# Akustikk_forsterkerkrets.net
KiCad netlist of a schematic drawn in Altium Designer
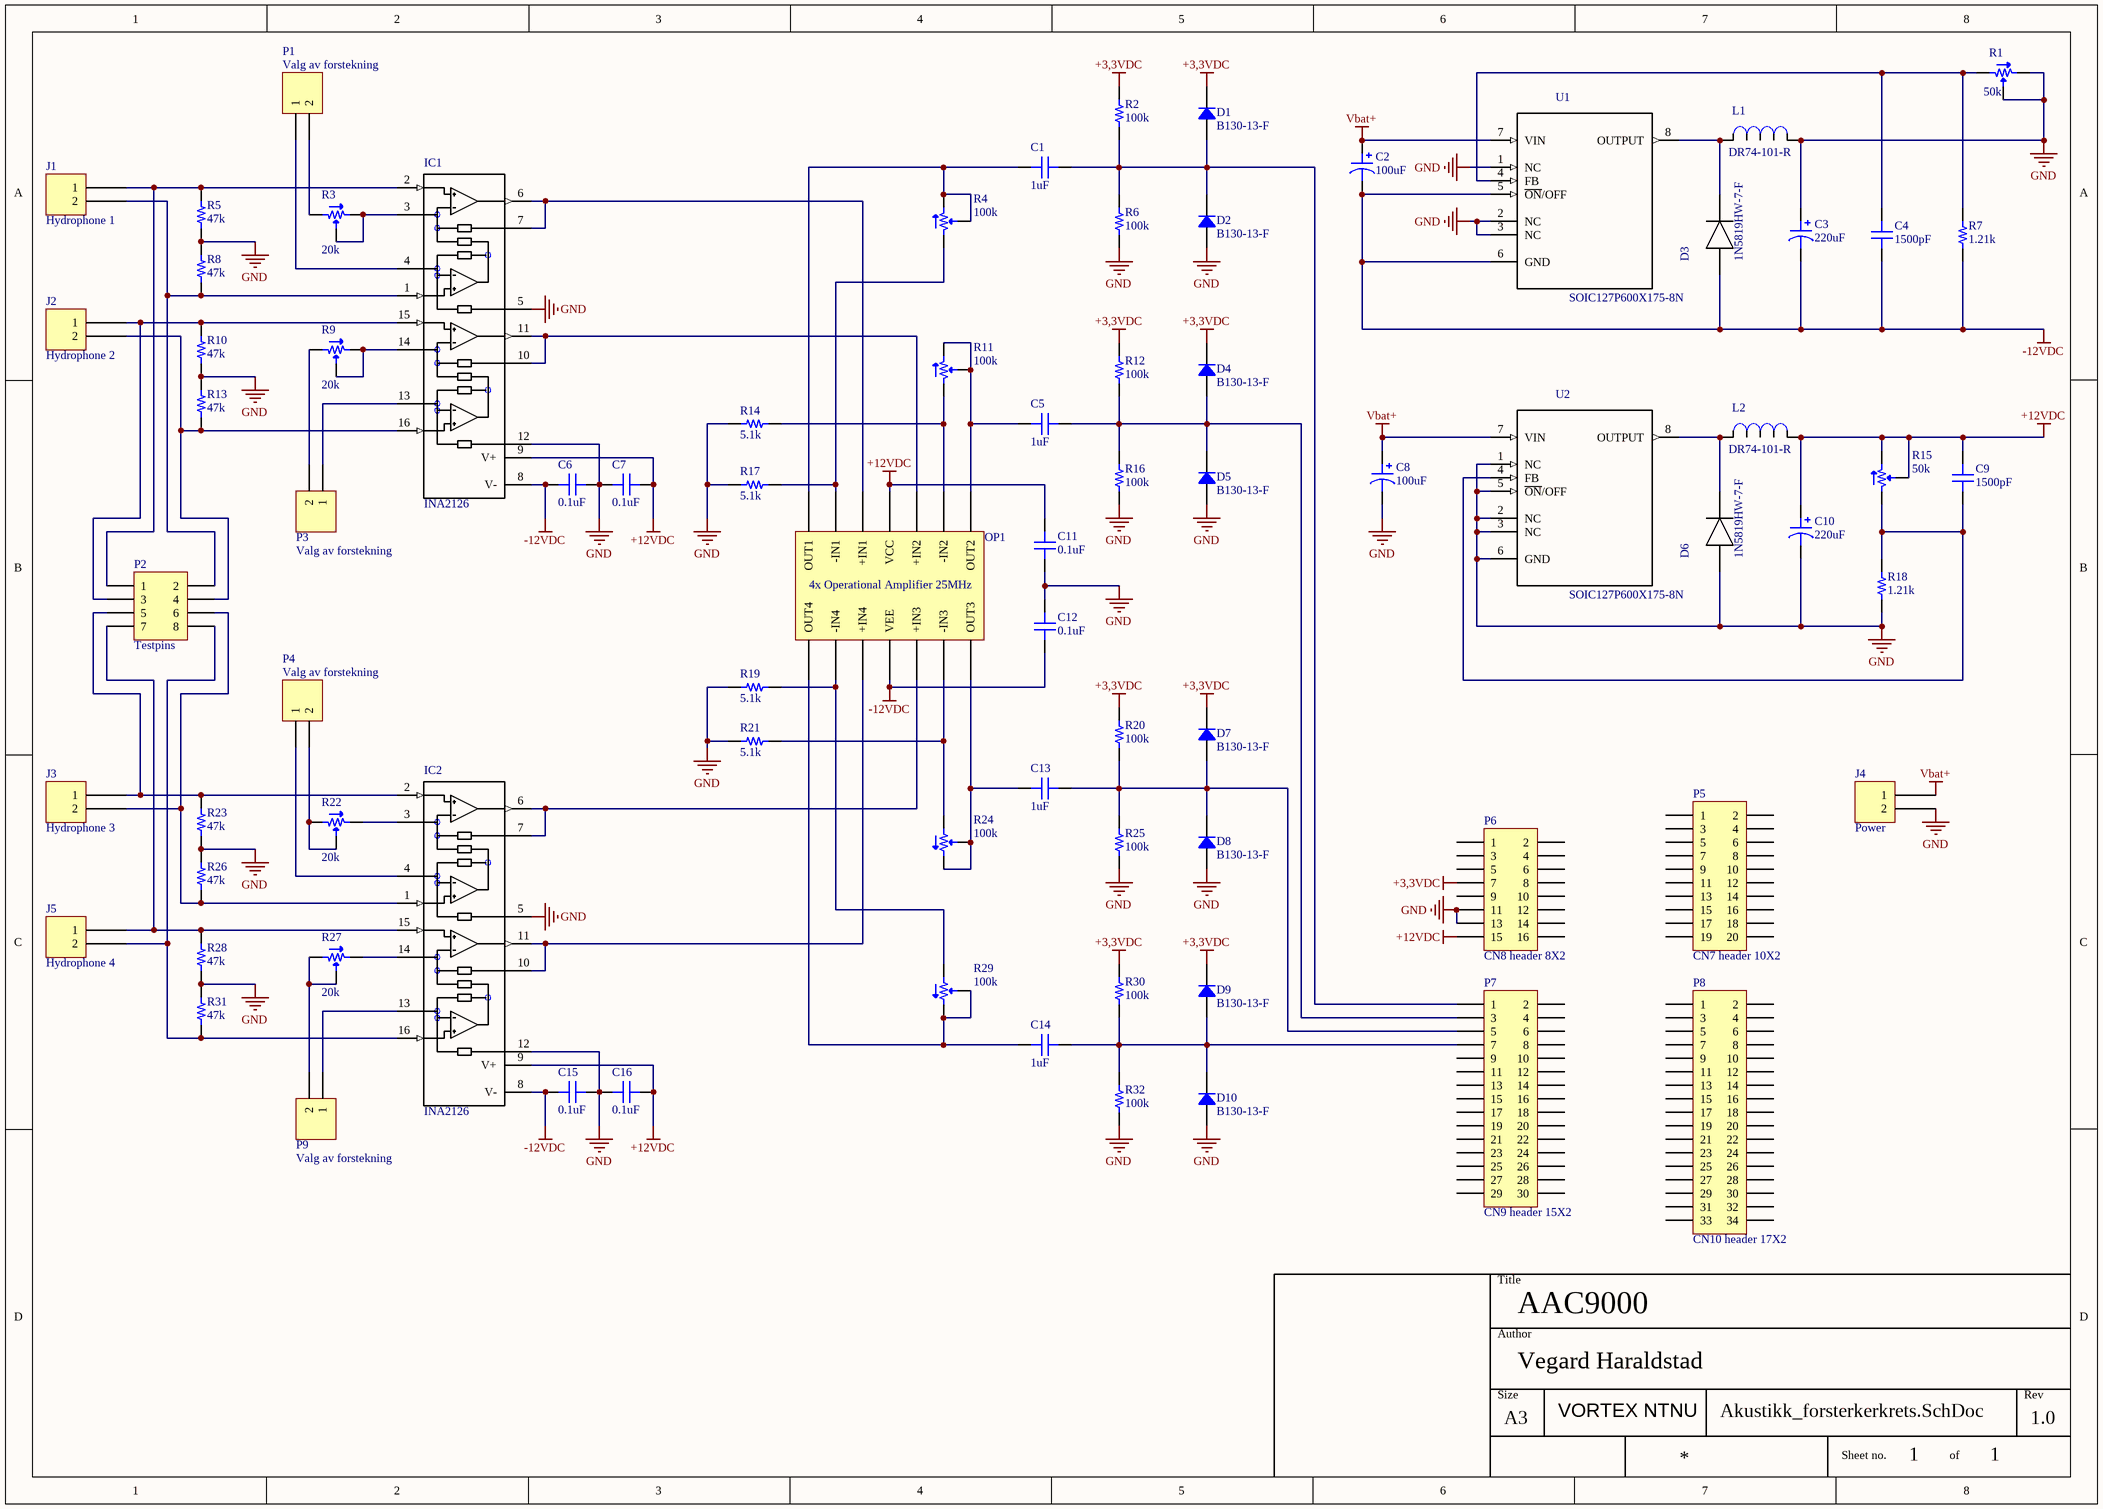
[diagram p0: Akustikk_forsterkerkrets.SchDoc]

(export (version "E")
  (design (tool "Eeschema 10.0.6"))
  (components
    (comp (ref "C1")
      (value "1uF")
      (footprint "CAP 0805/2012")
      (description "CAP CER 1UF 25V X7R 0805")
      (fields (field (name "PART NUMBER") "C0805C105J3RACTU") (field (name "MANUFACTURER") "Kemet"))
      (libsource (lib "Celestial Library Database") (part "Capacitor"))
    )
    (comp (ref "C2")
      (value "100uF")
      (footprint "CAP ALUM 10.3MM")
      (description "CAP ALUM 100UF 20% 50V SMD")
      (fields
        (field (name "PART NUMBER") "EEE-FC1H101P")
        (field (name "MANUFACTURER") "Panasonic Electronic Components")
      )
      (libsource (lib "Celestial Library Database") (part "Polarised Capacitor"))
    )
    (comp (ref "C3")
      (value "220uF")
      (footprint "CAP ALUM 6.6MM")
      (description "CAP ALUM 220UF 20% 25V SMD")
      (fields
        (field (name "PART NUMBER") "EEE-FTE221XAP")
        (field (name "MANUFACTURER") "Panasonic Electronic Components")
      )
      (libsource (lib "Celestial Library Database") (part "Polarised Capacitor"))
    )
    (comp (ref "C4")
      (value "1500pF")
      (footprint "CAP 0805/2012")
      (description "CAP CER 1500PF 50V C0G 0805")
      (fields
        (field (name "PART NUMBER") "C2012C0G1H152J060AA")
        (field (name "MANUFACTURER") "TDK Corporation")
      )
      (libsource (lib "Celestial Library Database") (part "Capacitor"))
    )
    (comp (ref "C5")
      (value "1uF")
      (footprint "CAP 0805/2012")
      (description "CAP CER 1UF 25V X7R 0805")
      (fields (field (name "PART NUMBER") "C0805C105J3RACTU") (field (name "MANUFACTURER") "Kemet"))
      (libsource (lib "Celestial Library Database") (part "Capacitor"))
    )
    (comp (ref "C6")
      (value "0.1uF")
      (footprint "CAP 0805/2012")
      (description "CAP CER 0.1UF 25V X7R 0805")
      (fields
        (field (name "PART NUMBER") "CL21B104KACNNNC")
        (field (name "MANUFACTURER") "Samsung Electro-Mechanics America, Inc.")
      )
      (libsource (lib "Celestial Library Database") (part "Capacitor"))
    )
    (comp (ref "C7")
      (value "0.1uF")
      (footprint "CAP 0805/2012")
      (description "CAP CER 0.1UF 25V X7R 0805")
      (fields
        (field (name "PART NUMBER") "CL21B104KACNNNC")
        (field (name "MANUFACTURER") "Samsung Electro-Mechanics America, Inc.")
      )
      (libsource (lib "Celestial Library Database") (part "Capacitor"))
    )
    (comp (ref "C8")
      (value "100uF")
      (footprint "CAP ALUM 10.3MM")
      (description "CAP ALUM 100UF 20% 50V SMD")
      (fields
        (field (name "PART NUMBER") "EEE-FC1H101P")
        (field (name "MANUFACTURER") "Panasonic Electronic Components")
      )
      (libsource (lib "Celestial Library Database") (part "Polarised Capacitor"))
    )
    (comp (ref "C9")
      (value "1500pF")
      (footprint "CAP 0805/2012")
      (description "CAP CER 1500PF 50V C0G 0805")
      (fields
        (field (name "PART NUMBER") "C2012C0G1H152J060AA")
        (field (name "MANUFACTURER") "TDK Corporation")
      )
      (libsource (lib "Celestial Library Database") (part "Capacitor"))
    )
    (comp (ref "C10")
      (value "220uF")
      (footprint "CAP ALUM 6.6MM")
      (description "CAP ALUM 220UF 20% 25V SMD")
      (fields
        (field (name "PART NUMBER") "EEE-FTE221XAP")
        (field (name "MANUFACTURER") "Panasonic Electronic Components")
      )
      (libsource (lib "Celestial Library Database") (part "Polarised Capacitor"))
    )
    (comp (ref "C11")
      (value "0.1uF")
      (footprint "CAP 0805/2012")
      (description "CAP CER 0.1UF 25V X7R 0805")
      (fields
        (field (name "PART NUMBER") "CL21B104KACNNNC")
        (field (name "MANUFACTURER") "Samsung Electro-Mechanics America, Inc.")
      )
      (libsource (lib "Celestial Library Database") (part "Capacitor"))
    )
    (comp (ref "C12")
      (value "0.1uF")
      (footprint "CAP 0805/2012")
      (description "CAP CER 0.1UF 25V X7R 0805")
      (fields
        (field (name "PART NUMBER") "CL21B104KACNNNC")
        (field (name "MANUFACTURER") "Samsung Electro-Mechanics America, Inc.")
      )
      (libsource (lib "Celestial Library Database") (part "Capacitor"))
    )
    (comp (ref "C13")
      (value "1uF")
      (footprint "CAP 0805/2012")
      (description "CAP CER 1UF 25V X7R 0805")
      (fields (field (name "PART NUMBER") "C0805C105J3RACTU") (field (name "MANUFACTURER") "Kemet"))
      (libsource (lib "Celestial Library Database") (part "Capacitor"))
    )
    (comp (ref "C14")
      (value "1uF")
      (footprint "CAP 0805/2012")
      (description "CAP CER 1UF 25V X7R 0805")
      (fields (field (name "PART NUMBER") "C0805C105J3RACTU") (field (name "MANUFACTURER") "Kemet"))
      (libsource (lib "Celestial Library Database") (part "Capacitor"))
    )
    (comp (ref "C15")
      (value "0.1uF")
      (footprint "CAP 0805/2012")
      (description "CAP CER 0.1UF 25V X7R 0805")
      (fields
        (field (name "PART NUMBER") "CL21B104KACNNNC")
        (field (name "MANUFACTURER") "Samsung Electro-Mechanics America, Inc.")
      )
      (libsource (lib "Celestial Library Database") (part "Capacitor"))
    )
    (comp (ref "C16")
      (value "0.1uF")
      (footprint "CAP 0805/2012")
      (description "CAP CER 0.1UF 25V X7R 0805")
      (fields
        (field (name "PART NUMBER") "CL21B104KACNNNC")
        (field (name "MANUFACTURER") "Samsung Electro-Mechanics America, Inc.")
      )
      (libsource (lib "Celestial Library Database") (part "Capacitor"))
    )
    (comp (ref "D1")
      (value "B130-13-F")
      (footprint "DO214AC SMA")
      (description "DIODE SCHOTTKY 30V 1A SMA")
      (fields (field (name "MANUFACTURER") "Diodes Incorporated"))
      (libsource (lib "Celestial Library Database") (part "Diode"))
    )
    (comp (ref "D2")
      (value "B130-13-F")
      (footprint "DO214AC SMA")
      (description "DIODE SCHOTTKY 30V 1A SMA")
      (fields (field (name "MANUFACTURER") "Diodes Incorporated"))
      (libsource (lib "Celestial Library Database") (part "Diode"))
    )
    (comp (ref "D3")
      (value "1N5819HW-7-F")
      (footprint "1N5819HW-7-F")
      (description "1N5819HW Series 40 V 1 A Surface Mount Schottky Barrier Rectifier - SOD-123")
      (fields (field (name "DIGI-KEY_PART_NUMBER") "1N5819HW-FDICT-ND") (field (name "MF") "Diodes Inc."))
      (libsource (lib "Vortex-component-database") (part "1N5819HW-7-F"))
    )
    (comp (ref "D4")
      (value "B130-13-F")
      (footprint "DO214AC SMA")
      (description "DIODE SCHOTTKY 30V 1A SMA")
      (fields (field (name "MANUFACTURER") "Diodes Incorporated"))
      (libsource (lib "Celestial Library Database") (part "Diode"))
    )
    (comp (ref "D5")
      (value "B130-13-F")
      (footprint "DO214AC SMA")
      (description "DIODE SCHOTTKY 30V 1A SMA")
      (fields (field (name "MANUFACTURER") "Diodes Incorporated"))
      (libsource (lib "Celestial Library Database") (part "Diode"))
    )
    (comp (ref "D6")
      (value "1N5819HW-7-F")
      (footprint "1N5819HW-7-F")
      (description "1N5819HW Series 40 V 1 A Surface Mount Schottky Barrier Rectifier - SOD-123")
      (fields (field (name "DIGI-KEY_PART_NUMBER") "1N5819HW-FDICT-ND") (field (name "MF") "Diodes Inc."))
      (libsource (lib "Vortex-component-database") (part "1N5819HW-7-F"))
    )
    (comp (ref "D7")
      (value "B130-13-F")
      (footprint "DO214AC SMA")
      (description "DIODE SCHOTTKY 30V 1A SMA")
      (fields (field (name "MANUFACTURER") "Diodes Incorporated"))
      (libsource (lib "Celestial Library Database") (part "Diode"))
    )
    (comp (ref "D8")
      (value "B130-13-F")
      (footprint "DO214AC SMA")
      (description "DIODE SCHOTTKY 30V 1A SMA")
      (fields (field (name "MANUFACTURER") "Diodes Incorporated"))
      (libsource (lib "Celestial Library Database") (part "Diode"))
    )
    (comp (ref "D9")
      (value "B130-13-F")
      (footprint "DO214AC SMA")
      (description "DIODE SCHOTTKY 30V 1A SMA")
      (fields (field (name "MANUFACTURER") "Diodes Incorporated"))
      (libsource (lib "Celestial Library Database") (part "Diode"))
    )
    (comp (ref "D10")
      (value "B130-13-F")
      (footprint "DO214AC SMA")
      (description "DIODE SCHOTTKY 30V 1A SMA")
      (fields (field (name "MANUFACTURER") "Diodes Incorporated"))
      (libsource (lib "Celestial Library Database") (part "Diode"))
    )
    (comp (ref "IC1")
      (value "INA2126")
      (footprint "SOP63P600X175-16N")
      (fields (field (name "MF") "Texas Instruments") (field (name "PART NUMBER") "INA2126EA/250"))
      (libsource (lib "Vortex-component-database") (part "INA2126"))
    )
    (comp (ref "IC2")
      (value "INA2126")
      (footprint "SOP63P600X175-16N")
      (fields (field (name "MF") "Texas Instruments") (field (name "PART NUMBER") "INA2126EA/250"))
      (libsource (lib "Vortex-component-database") (part "INA2126"))
    )
    (comp (ref "J1")
      (value "Hydrophone 1")
      (footprint "JST XH B2B-XH-A")
      (description "CONN HEADER XH TOP 2POS 2.5MM")
      (fields
        (field (name "PART NUMBER") "B2B-XH-A(LF)(SN)")
        (field (name "MANUFACTURER") "JST Sales America Inc.")
      )
      (libsource (lib "Celestial Library Database") (part "2 Pin"))
    )
    (comp (ref "J2")
      (value "Hydrophone 2")
      (footprint "JST XH B2B-XH-A")
      (description "CONN HEADER XH TOP 2POS 2.5MM")
      (fields
        (field (name "PART NUMBER") "B2B-XH-A(LF)(SN)")
        (field (name "MANUFACTURER") "JST Sales America Inc.")
      )
      (libsource (lib "Celestial Library Database") (part "2 Pin"))
    )
    (comp (ref "J3")
      (value "Hydrophone 3")
      (footprint "JST XH B2B-XH-A")
      (description "CONN HEADER XH TOP 2POS 2.5MM")
      (fields
        (field (name "PART NUMBER") "B2B-XH-A(LF)(SN)")
        (field (name "MANUFACTURER") "JST Sales America Inc.")
      )
      (libsource (lib "Celestial Library Database") (part "2 Pin"))
    )
    (comp (ref "J4")
      (value "Power")
      (footprint "JST XH B2B-XH-A")
      (description "CONN HEADER XH TOP 2POS 2.5MM")
      (fields
        (field (name "PART NUMBER") "B2B-XH-A(LF)(SN)")
        (field (name "MANUFACTURER") "JST Sales America Inc.")
      )
      (libsource (lib "Celestial Library Database") (part "2 Pin"))
    )
    (comp (ref "J5")
      (value "Hydrophone 4")
      (footprint "JST XH B2B-XH-A")
      (description "CONN HEADER XH TOP 2POS 2.5MM")
      (fields
        (field (name "PART NUMBER") "B2B-XH-A(LF)(SN)")
        (field (name "MANUFACTURER") "JST Sales America Inc.")
      )
      (libsource (lib "Celestial Library Database") (part "2 Pin"))
    )
    (comp (ref "L1")
      (value "DR74-101-R")
      (footprint "DR74-101-R")
      (description "Inductor Power Shielded Drum Core 101.6uH/100uH 20% 100KHz Ferrite 860mA 383mOhm DCR T/R")
      (fields (field (name "MF") "Eaton"))
      (libsource (lib "Vortex-component-database") (part "DR74-101-R"))
    )
    (comp (ref "L2")
      (value "DR74-101-R")
      (footprint "DR74-101-R")
      (description "Inductor Power Shielded Drum Core 101.6uH/100uH 20% 100KHz Ferrite 860mA 383mOhm DCR T/R")
      (fields (field (name "MF") "Eaton"))
      (libsource (lib "Vortex-component-database") (part "DR74-101-R"))
    )
    (comp (ref "OP1")
      (value "4x Operational Amplifier 25MHz")
      (footprint "SOIC127P600X175-14N")
      (fields (field (name "PART NUMBER") "LM837MX/NOPB"))
      (libsource (lib "Vortex-component-database") (part "LM837MX/NOPB"))
    )
    (comp (ref "P1")
      (value "Valg av forstekning")
      (footprint "HDR1X2")
      (description "Header, 2-Pin")
      (fields (field (name "PUBLISHER") "Altium Limited"))
      (libsource (lib "") (part "Header 2_1"))
    )
    (comp (ref "P2")
      (value "Testpins")
      (footprint "HDR2X4")
      (description "Header, 4-Pin, Dual row")
      (fields (field (name "PUBLISHER") "Altium Limited"))
      (libsource (lib "Miscellaneous Connectors") (part "Header 4X2"))
    )
    (comp (ref "P3")
      (value "Valg av forstekning")
      (footprint "HDR1X2")
      (description "Header, 2-Pin")
      (fields (field (name "PUBLISHER") "Altium Limited"))
      (libsource (lib "Miscellaneous Connectors") (part "Header 2"))
    )
    (comp (ref "P4")
      (value "Valg av forstekning")
      (footprint "HDR1X2")
      (description "Header, 2-Pin")
      (fields (field (name "PUBLISHER") "Altium Limited"))
      (libsource (lib "") (part "Header 2_1"))
    )
    (comp (ref "P5")
      (value "CN7 header 10X2")
      (footprint "HDR2X10")
      (description "Header, 10-Pin, Dual row")
      (fields (field (name "PUBLISHER") "Altium Limited"))
      (libsource (lib "Miscellaneous Connectors") (part "Header 10X2"))
    )
    (comp (ref "P6")
      (value "CN8 header 8X2")
      (footprint "HDR2X8")
      (description "Header, 8-Pin, Dual row")
      (fields (field (name "PUBLISHER") "Altium Limited"))
      (libsource (lib "Miscellaneous Connectors") (part "Header 8X2"))
    )
    (comp (ref "P7")
      (value "CN9 header 15X2")
      (footprint "HDR2X15")
      (description "Header, 15-Pin, Dual row")
      (fields (field (name "PUBLISHER") "Altium Limited"))
      (libsource (lib "Miscellaneous Connectors") (part "Header 15X2"))
    )
    (comp (ref "P8")
      (value "CN10 header 17X2")
      (footprint "HDR2X17")
      (description "Header, 17-Pin, Dual row")
      (fields (field (name "PUBLISHER") "Altium Limited"))
      (libsource (lib "Miscellaneous Connectors") (part "Header 17X2"))
    )
    (comp (ref "P9")
      (value "Valg av forstekning")
      (footprint "HDR1X2")
      (description "Header, 2-Pin")
      (fields (field (name "PUBLISHER") "Altium Limited"))
      (libsource (lib "Miscellaneous Connectors") (part "Header 2"))
    )
    (comp (ref "R1")
      (value "50k")
      (footprint "POT BOURNS TRIMPOT 3302")
      (description "TRIMMER 20K OHM 0.15W SMD")
      (fields (field (name "PART NUMBER") "3302W-3-203E") (field (name "MANUFACTURER") "Bourns Inc."))
      (libsource (lib "Celestial Library Database") (part "Potentiometer"))
    )
    (comp (ref "R2")
      (value "100k")
      (footprint "RES 0805/2012")
      (description "RES SMD 100K OHM 5% 1/8W 0805")
      (fields
        (field (name "PART NUMBER") "ERJ-6GEYJ104V")
        (field (name "MANUFACTURER") "Panasonic Electronic Components")
      )
      (libsource (lib "Celestial Library Database") (part "Resistor"))
    )
    (comp (ref "R3")
      (value "20k")
      (footprint "POT BOURNS TRIMPOT 3302")
      (description "TRIMMER 20K OHM 0.15W SMD")
      (fields (field (name "PART NUMBER") "3302W-3-203E") (field (name "MANUFACTURER") "Bourns Inc."))
      (libsource (lib "Celestial Library Database") (part "Potentiometer"))
    )
    (comp (ref "R4")
      (value "100k")
      (footprint "POT BOURNS TRIMPOT 3302")
      (description "TRIMMER 20K OHM 0.15W SMD")
      (fields (field (name "PART NUMBER") "3302W-3-203E") (field (name "MANUFACTURER") "Bourns Inc."))
      (libsource (lib "Celestial Library Database") (part "Potentiometer"))
    )
    (comp (ref "R5")
      (value "47k")
      (footprint "RES 0805/2012")
      (description "RES SMD 47K OHM 1% 1/8W 0805")
      (fields
        (field (name "PART NUMBER") "ERJ-6ENF4702V")
        (field (name "MANUFACTURER") "Panasonic Electronic Components")
      )
      (libsource (lib "Celestial Library Database") (part "Resistor"))
    )
    (comp (ref "R6")
      (value "100k")
      (footprint "RES 0805/2012")
      (description "RES SMD 100K OHM 5% 1/8W 0805")
      (fields
        (field (name "PART NUMBER") "ERJ-6GEYJ104V")
        (field (name "MANUFACTURER") "Panasonic Electronic Components")
      )
      (libsource (lib "Celestial Library Database") (part "Resistor"))
    )
    (comp (ref "R7")
      (value "1.21k")
      (footprint "RES 0805/2012")
      (description "RES SMD 1.21K OHM 0.1% 1/8W 0805")
      (fields
        (field (name "PART NUMBER") "ERA-6AEB1211V")
        (field (name "MANUFACTURER") "Panasonic Electronic Components")
      )
      (libsource (lib "Celestial Library Database") (part "Resistor"))
    )
    (comp (ref "R8")
      (value "47k")
      (footprint "RES 0805/2012")
      (description "RES SMD 47K OHM 1% 1/8W 0805")
      (fields
        (field (name "PART NUMBER") "ERJ-6ENF4702V")
        (field (name "MANUFACTURER") "Panasonic Electronic Components")
      )
      (libsource (lib "Celestial Library Database") (part "Resistor"))
    )
    (comp (ref "R9")
      (value "20k")
      (footprint "POT BOURNS TRIMPOT 3302")
      (description "TRIMMER 20K OHM 0.15W SMD")
      (fields (field (name "PART NUMBER") "3302W-3-203E") (field (name "MANUFACTURER") "Bourns Inc."))
      (libsource (lib "Celestial Library Database") (part "Potentiometer"))
    )
    (comp (ref "R10")
      (value "47k")
      (footprint "RES 0805/2012")
      (description "RES SMD 47K OHM 1% 1/8W 0805")
      (fields
        (field (name "PART NUMBER") "ERJ-6ENF4702V")
        (field (name "MANUFACTURER") "Panasonic Electronic Components")
      )
      (libsource (lib "Celestial Library Database") (part "Resistor"))
    )
    (comp (ref "R11")
      (value "100k")
      (footprint "POT BOURNS TRIMPOT 3302")
      (description "TRIMMER 20K OHM 0.15W SMD")
      (fields (field (name "PART NUMBER") "3302W-3-203E") (field (name "MANUFACTURER") "Bourns Inc."))
      (libsource (lib "Celestial Library Database") (part "Potentiometer"))
    )
    (comp (ref "R12")
      (value "100k")
      (footprint "RES 0805/2012")
      (description "RES SMD 100K OHM 5% 1/8W 0805")
      (fields
        (field (name "PART NUMBER") "ERJ-6GEYJ104V")
        (field (name "MANUFACTURER") "Panasonic Electronic Components")
      )
      (libsource (lib "Celestial Library Database") (part "Resistor"))
    )
    (comp (ref "R13")
      (value "47k")
      (footprint "RES 0805/2012")
      (description "RES SMD 47K OHM 1% 1/8W 0805")
      (fields
        (field (name "PART NUMBER") "ERJ-6ENF4702V")
        (field (name "MANUFACTURER") "Panasonic Electronic Components")
      )
      (libsource (lib "Celestial Library Database") (part "Resistor"))
    )
    (comp (ref "R14")
      (value "5.1k")
      (footprint "RES 0805/2012")
      (description "RES SMD 5.1K OHM 1% 1/8W 0805")
      (fields
        (field (name "PART NUMBER") "ERJ-6ENF5101V")
        (field (name "MANUFACTURER") "Panasonic Electronic Components")
      )
      (libsource (lib "Celestial Library Database") (part "Resistor"))
    )
    (comp (ref "R15")
      (value "50k")
      (footprint "POT BOURNS TRIMPOT 3302")
      (description "TRIMMER 20K OHM 0.15W SMD")
      (fields (field (name "PART NUMBER") "3302W-3-203E") (field (name "MANUFACTURER") "Bourns Inc."))
      (libsource (lib "Celestial Library Database") (part "Potentiometer"))
    )
    (comp (ref "R16")
      (value "100k")
      (footprint "RES 0805/2012")
      (description "RES SMD 100K OHM 5% 1/8W 0805")
      (fields
        (field (name "PART NUMBER") "ERJ-6GEYJ104V")
        (field (name "MANUFACTURER") "Panasonic Electronic Components")
      )
      (libsource (lib "Celestial Library Database") (part "Resistor"))
    )
    (comp (ref "R17")
      (value "5.1k")
      (footprint "RES 0805/2012")
      (description "RES SMD 5.1K OHM 1% 1/8W 0805")
      (fields
        (field (name "PART NUMBER") "ERJ-6ENF5101V")
        (field (name "MANUFACTURER") "Panasonic Electronic Components")
      )
      (libsource (lib "Celestial Library Database") (part "Resistor"))
    )
    (comp (ref "R18")
      (value "1.21k")
      (footprint "RES 0805/2012")
      (description "RES SMD 1.21K OHM 0.1% 1/8W 0805")
      (fields
        (field (name "PART NUMBER") "ERA-6AEB1211V")
        (field (name "MANUFACTURER") "Panasonic Electronic Components")
      )
      (libsource (lib "Celestial Library Database") (part "Resistor"))
    )
    (comp (ref "R19")
      (value "5.1k")
      (footprint "RES 0805/2012")
      (description "RES SMD 5.1K OHM 1% 1/8W 0805")
      (fields
        (field (name "PART NUMBER") "ERJ-6ENF5101V")
        (field (name "MANUFACTURER") "Panasonic Electronic Components")
      )
      (libsource (lib "Celestial Library Database") (part "Resistor"))
    )
    (comp (ref "R20")
      (value "100k")
      (footprint "RES 0805/2012")
      (description "RES SMD 100K OHM 5% 1/8W 0805")
      (fields
        (field (name "PART NUMBER") "ERJ-6GEYJ104V")
        (field (name "MANUFACTURER") "Panasonic Electronic Components")
      )
      (libsource (lib "Celestial Library Database") (part "Resistor"))
    )
    (comp (ref "R21")
      (value "5.1k")
      (footprint "RES 0805/2012")
      (description "RES SMD 5.1K OHM 1% 1/8W 0805")
      (fields
        (field (name "PART NUMBER") "ERJ-6ENF5101V")
        (field (name "MANUFACTURER") "Panasonic Electronic Components")
      )
      (libsource (lib "Celestial Library Database") (part "Resistor"))
    )
    (comp (ref "R22")
      (value "20k")
      (footprint "POT BOURNS TRIMPOT 3302")
      (description "TRIMMER 20K OHM 0.15W SMD")
      (fields (field (name "PART NUMBER") "3302W-3-203E") (field (name "MANUFACTURER") "Bourns Inc."))
      (libsource (lib "Celestial Library Database") (part "Potentiometer"))
    )
    (comp (ref "R23")
      (value "47k")
      (footprint "RES 0805/2012")
      (description "RES SMD 47K OHM 1% 1/8W 0805")
      (fields
        (field (name "PART NUMBER") "ERJ-6ENF4702V")
        (field (name "MANUFACTURER") "Panasonic Electronic Components")
      )
      (libsource (lib "Celestial Library Database") (part "Resistor"))
    )
    (comp (ref "R24")
      (value "100k")
      (footprint "POT BOURNS TRIMPOT 3302")
      (description "TRIMMER 20K OHM 0.15W SMD")
      (fields (field (name "PART NUMBER") "3302W-3-203E") (field (name "MANUFACTURER") "Bourns Inc."))
      (libsource (lib "Celestial Library Database") (part "Potentiometer"))
    )
    (comp (ref "R25")
      (value "100k")
      (footprint "RES 0805/2012")
      (description "RES SMD 100K OHM 5% 1/8W 0805")
      (fields
        (field (name "PART NUMBER") "ERJ-6GEYJ104V")
        (field (name "MANUFACTURER") "Panasonic Electronic Components")
      )
      (libsource (lib "Celestial Library Database") (part "Resistor"))
    )
    (comp (ref "R26")
      (value "47k")
      (footprint "RES 0805/2012")
      (description "RES SMD 47K OHM 1% 1/8W 0805")
      (fields
        (field (name "PART NUMBER") "ERJ-6ENF4702V")
        (field (name "MANUFACTURER") "Panasonic Electronic Components")
      )
      (libsource (lib "Celestial Library Database") (part "Resistor"))
    )
    (comp (ref "R27")
      (value "20k")
      (footprint "POT BOURNS TRIMPOT 3302")
      (description "TRIMMER 20K OHM 0.15W SMD")
      (fields (field (name "PART NUMBER") "3302W-3-203E") (field (name "MANUFACTURER") "Bourns Inc."))
      (libsource (lib "Celestial Library Database") (part "Potentiometer"))
    )
    (comp (ref "R28")
      (value "47k")
      (footprint "RES 0805/2012")
      (description "RES SMD 47K OHM 1% 1/8W 0805")
      (fields
        (field (name "PART NUMBER") "ERJ-6ENF4702V")
        (field (name "MANUFACTURER") "Panasonic Electronic Components")
      )
      (libsource (lib "Celestial Library Database") (part "Resistor"))
    )
    (comp (ref "R29")
      (value "100k")
      (footprint "POT BOURNS TRIMPOT 3302")
      (description "TRIMMER 20K OHM 0.15W SMD")
      (fields (field (name "PART NUMBER") "3302W-3-203E") (field (name "MANUFACTURER") "Bourns Inc."))
      (libsource (lib "Celestial Library Database") (part "Potentiometer"))
    )
    (comp (ref "R30")
      (value "100k")
      (footprint "RES 0805/2012")
      (description "RES SMD 100K OHM 5% 1/8W 0805")
      (fields
        (field (name "PART NUMBER") "ERJ-6GEYJ104V")
        (field (name "MANUFACTURER") "Panasonic Electronic Components")
      )
      (libsource (lib "Celestial Library Database") (part "Resistor"))
    )
    (comp (ref "R31")
      (value "47k")
      (footprint "RES 0805/2012")
      (description "RES SMD 47K OHM 1% 1/8W 0805")
      (fields
        (field (name "PART NUMBER") "ERJ-6ENF4702V")
        (field (name "MANUFACTURER") "Panasonic Electronic Components")
      )
      (libsource (lib "Celestial Library Database") (part "Resistor"))
    )
    (comp (ref "R32")
      (value "100k")
      (footprint "RES 0805/2012")
      (description "RES SMD 100K OHM 5% 1/8W 0805")
      (fields
        (field (name "PART NUMBER") "ERJ-6GEYJ104V")
        (field (name "MANUFACTURER") "Panasonic Electronic Components")
      )
      (libsource (lib "Celestial Library Database") (part "Resistor"))
    )
    (comp (ref "U1")
      (value "SOIC127P600X175-8N")
      (footprint "SOIC127P600X175-8N")
      (description "SIMPLE SWITCHERÂ® 40V, 500mA Low Component Count Step-Down Regulator 8-SOIC -40 to 125")
      (fields (field (name "MP") "LM2674MX-12/NOPB") (field (name "MF") "Texas Instruments"))
      (libsource (lib "Vortex-component-database") (part "SOIC127P600X175-8N"))
    )
    (comp (ref "U2")
      (value "SOIC127P600X175-8N")
      (footprint "SOIC127P600X175-8N")
      (description "SIMPLE SWITCHERÂ® 40V, 500mA Low Component Count Step-Down Regulator 8-SOIC -40 to 125")
      (fields (field (name "MP") "LM2674MX-12/NOPB") (field (name "MF") "Texas Instruments"))
      (libsource (lib "Vortex-component-database") (part "SOIC127P600X175-8N"))
    )
  )
  (nets
    (net (code "1") (name "+3,3VDC") (class "Default")
      (node (ref "D1") (pin "2") (pinfunction "2_2") (pintype "passive"))
      (node (ref "D4") (pin "2") (pinfunction "2_2") (pintype "passive"))
      (node (ref "D7") (pin "2") (pinfunction "2_2") (pintype "passive"))
      (node (ref "D9") (pin "2") (pinfunction "2_2") (pintype "passive"))
      (node (ref "P6") (pin "7") (pinfunction "7_7") (pintype "passive"))
      (node (ref "R12") (pin "2") (pinfunction "2_2") (pintype "passive"))
      (node (ref "R2") (pin "2") (pinfunction "2_2") (pintype "passive"))
      (node (ref "R20") (pin "2") (pinfunction "2_2") (pintype "passive"))
      (node (ref "R30") (pin "2") (pinfunction "2_2") (pintype "passive"))
    )
    (net (code "2") (name "+12VDC") (class "Default")
      (node (ref "C10") (pin "1") (pinfunction "1_1") (pintype "passive"))
      (node (ref "C11") (pin "2") (pinfunction "2_2") (pintype "passive"))
      (node (ref "C16") (pin "2") (pinfunction "2_2") (pintype "passive"))
      (node (ref "C7") (pin "2") (pinfunction "2_2") (pintype "passive"))
      (node (ref "C9") (pin "2") (pinfunction "2_2") (pintype "passive"))
      (node (ref "IC1") (pin "9") (pinfunction "V+_9") (pintype "power_in"))
      (node (ref "IC2") (pin "9") (pinfunction "V+_9") (pintype "power_in"))
      (node (ref "L2") (pin "1") (pinfunction "1_1") (pintype "passive"))
      (node (ref "OP1") (pin "4") (pinfunction "VCC_4") (pintype "passive"))
      (node (ref "P6") (pin "15") (pinfunction "15_15") (pintype "passive"))
      (node (ref "R15") (pin "2") (pinfunction "2_2") (pintype "passive"))
      (node (ref "R15") (pin "3") (pinfunction "3_3") (pintype "passive"))
    )
    (net (code "3") (name "-12VDC") (class "Default")
      (node (ref "C12") (pin "1") (pinfunction "1_1") (pintype "passive"))
      (node (ref "C15") (pin "1") (pinfunction "1_1") (pintype "passive"))
      (node (ref "C2") (pin "2") (pinfunction "2_2") (pintype "passive"))
      (node (ref "C3") (pin "2") (pinfunction "2_2") (pintype "passive"))
      (node (ref "C4") (pin "1") (pinfunction "1_1") (pintype "passive"))
      (node (ref "C6") (pin "1") (pinfunction "1_1") (pintype "passive"))
      (node (ref "D3") (pin "2") (pinfunction "A_2") (pintype "passive"))
      (node (ref "IC1") (pin "8") (pinfunction "V-_8") (pintype "power_in"))
      (node (ref "IC2") (pin "8") (pinfunction "V-_8") (pintype "power_in"))
      (node (ref "OP1") (pin "11") (pinfunction "VEE_11") (pintype "passive"))
      (node (ref "R7") (pin "1") (pinfunction "1_1") (pintype "passive"))
      (node (ref "U1") (pin "5") (pinfunction "~{ON}/OFF_5") (pintype "input"))
      (node (ref "U1") (pin "6") (pinfunction "GND_6") (pintype "passive"))
    )
    (net (code "4") (name "GND") (class "Default")
      (node (ref "C10") (pin "2") (pinfunction "2_2") (pintype "passive"))
      (node (ref "C11") (pin "1") (pinfunction "1_1") (pintype "passive"))
      (node (ref "C12") (pin "2") (pinfunction "2_2") (pintype "passive"))
      (node (ref "C15") (pin "2") (pinfunction "2_2") (pintype "passive"))
      (node (ref "C16") (pin "1") (pinfunction "1_1") (pintype "passive"))
      (node (ref "C3") (pin "1") (pinfunction "1_1") (pintype "passive"))
      (node (ref "C6") (pin "2") (pinfunction "2_2") (pintype "passive"))
      (node (ref "C7") (pin "1") (pinfunction "1_1") (pintype "passive"))
      (node (ref "C8") (pin "2") (pinfunction "2_2") (pintype "passive"))
      (node (ref "D10") (pin "1") (pinfunction "1_1") (pintype "passive"))
      (node (ref "D2") (pin "1") (pinfunction "1_1") (pintype "passive"))
      (node (ref "D5") (pin "1") (pinfunction "1_1") (pintype "passive"))
      (node (ref "D6") (pin "2") (pinfunction "A_2") (pintype "passive"))
      (node (ref "D8") (pin "1") (pinfunction "1_1") (pintype "passive"))
      (node (ref "IC1") (pin "12") (pinfunction "REFB_12") (pintype "power_in"))
      (node (ref "IC1") (pin "5") (pinfunction "REFA_5") (pintype "power_in"))
      (node (ref "IC2") (pin "12") (pinfunction "REFB_12") (pintype "power_in"))
      (node (ref "IC2") (pin "5") (pinfunction "REFA_5") (pintype "power_in"))
      (node (ref "J4") (pin "2") (pinfunction "2_2") (pintype "passive"))
      (node (ref "L1") (pin "1") (pinfunction "1_1") (pintype "passive"))
      (node (ref "P6") (pin "11") (pinfunction "11_11") (pintype "passive"))
      (node (ref "P6") (pin "13") (pinfunction "13_13") (pintype "passive"))
      (node (ref "R1") (pin "2") (pinfunction "2_2") (pintype "passive"))
      (node (ref "R1") (pin "3") (pinfunction "3_3") (pintype "passive"))
      (node (ref "R10") (pin "1") (pinfunction "1_1") (pintype "passive"))
      (node (ref "R13") (pin "2") (pinfunction "2_2") (pintype "passive"))
      (node (ref "R14") (pin "2") (pinfunction "2_2") (pintype "passive"))
      (node (ref "R16") (pin "1") (pinfunction "1_1") (pintype "passive"))
      (node (ref "R17") (pin "2") (pinfunction "2_2") (pintype "passive"))
      (node (ref "R18") (pin "1") (pinfunction "1_1") (pintype "passive"))
      (node (ref "R19") (pin "2") (pinfunction "2_2") (pintype "passive"))
      (node (ref "R21") (pin "2") (pinfunction "2_2") (pintype "passive"))
      (node (ref "R23") (pin "1") (pinfunction "1_1") (pintype "passive"))
      (node (ref "R25") (pin "1") (pinfunction "1_1") (pintype "passive"))
      (node (ref "R26") (pin "2") (pinfunction "2_2") (pintype "passive"))
      (node (ref "R28") (pin "1") (pinfunction "1_1") (pintype "passive"))
      (node (ref "R31") (pin "2") (pinfunction "2_2") (pintype "passive"))
      (node (ref "R32") (pin "1") (pinfunction "1_1") (pintype "passive"))
      (node (ref "R5") (pin "1") (pinfunction "1_1") (pintype "passive"))
      (node (ref "R6") (pin "1") (pinfunction "1_1") (pintype "passive"))
      (node (ref "R8") (pin "2") (pinfunction "2_2") (pintype "passive"))
      (node (ref "U1") (pin "1") (pinfunction "NC_1") (pintype "input"))
      (node (ref "U1") (pin "2") (pinfunction "NC_2") (pintype "passive"))
      (node (ref "U1") (pin "3") (pinfunction "NC_3") (pintype "passive"))
      (node (ref "U2") (pin "1") (pinfunction "NC_1") (pintype "input"))
      (node (ref "U2") (pin "2") (pinfunction "NC_2") (pintype "passive"))
      (node (ref "U2") (pin "3") (pinfunction "NC_3") (pintype "passive"))
      (node (ref "U2") (pin "5") (pinfunction "~{ON}/OFF_5") (pintype "input"))
      (node (ref "U2") (pin "6") (pinfunction "GND_6") (pintype "passive"))
    )
    (net (code "5") (name "Net-(C1-Pad2)") (class "Default")
      (node (ref "C1") (pin "2") (pinfunction "2_2") (pintype "passive"))
      (node (ref "D1") (pin "1") (pinfunction "1_1") (pintype "passive"))
      (node (ref "D2") (pin "2") (pinfunction "2_2") (pintype "passive"))
      (node (ref "P7") (pin "1") (pinfunction "1_1") (pintype "passive"))
      (node (ref "R2") (pin "1") (pinfunction "1_1") (pintype "passive"))
      (node (ref "R6") (pin "2") (pinfunction "2_2") (pintype "passive"))
    )
    (net (code "6") (name "Net-(C5-Pad2)") (class "Default")
      (node (ref "C5") (pin "2") (pinfunction "2_2") (pintype "passive"))
      (node (ref "D4") (pin "1") (pinfunction "1_1") (pintype "passive"))
      (node (ref "D5") (pin "2") (pinfunction "2_2") (pintype "passive"))
      (node (ref "P7") (pin "3") (pinfunction "3_3") (pintype "passive"))
      (node (ref "R12") (pin "1") (pinfunction "1_1") (pintype "passive"))
      (node (ref "R16") (pin "2") (pinfunction "2_2") (pintype "passive"))
    )
    (net (code "7") (name "Net-(C13-Pad2)") (class "Default")
      (node (ref "C13") (pin "2") (pinfunction "2_2") (pintype "passive"))
      (node (ref "D7") (pin "1") (pinfunction "1_1") (pintype "passive"))
      (node (ref "D8") (pin "2") (pinfunction "2_2") (pintype "passive"))
      (node (ref "P7") (pin "5") (pinfunction "5_5") (pintype "passive"))
      (node (ref "R20") (pin "1") (pinfunction "1_1") (pintype "passive"))
      (node (ref "R25") (pin "2") (pinfunction "2_2") (pintype "passive"))
    )
    (net (code "8") (name "Net-(C14-Pad2)") (class "Default")
      (node (ref "C14") (pin "2") (pinfunction "2_2") (pintype "passive"))
      (node (ref "D10") (pin "2") (pinfunction "2_2") (pintype "passive"))
      (node (ref "D9") (pin "1") (pinfunction "1_1") (pintype "passive"))
      (node (ref "P7") (pin "7") (pinfunction "7_7") (pintype "passive"))
      (node (ref "R30") (pin "1") (pinfunction "1_1") (pintype "passive"))
      (node (ref "R32") (pin "2") (pinfunction "2_2") (pintype "passive"))
    )
    (net (code "9") (name "Net-(D3-C)") (class "Default")
      (node (ref "D3") (pin "1") (pinfunction "C_1") (pintype "passive"))
      (node (ref "L1") (pin "2") (pinfunction "2_2") (pintype "passive"))
      (node (ref "U1") (pin "8") (pinfunction "OUTPUT_8") (pintype "output"))
    )
    (net (code "10") (name "Net-(D6-C)") (class "Default")
      (node (ref "D6") (pin "1") (pinfunction "C_1") (pintype "passive"))
      (node (ref "L2") (pin "2") (pinfunction "2_2") (pintype "passive"))
      (node (ref "U2") (pin "8") (pinfunction "OUTPUT_8") (pintype "output"))
    )
    (net (code "11") (name "Net-(IC1-+INA)") (class "Default")
      (node (ref "IC1") (pin "2") (pinfunction "+INA_2") (pintype "input"))
      (node (ref "J1") (pin "1") (pinfunction "1_1") (pintype "passive"))
      (node (ref "P2") (pin "1") (pinfunction "1_1") (pintype "passive"))
      (node (ref "R5") (pin "2") (pinfunction "2_2") (pintype "passive"))
    )
    (net (code "12") (name "Net-(IC1-+INB)") (class "Default")
      (node (ref "IC1") (pin "15") (pinfunction "+INB_15") (pintype "input"))
      (node (ref "J2") (pin "1") (pinfunction "1_1") (pintype "passive"))
      (node (ref "P2") (pin "3") (pinfunction "3_3") (pintype "passive"))
      (node (ref "R10") (pin "2") (pinfunction "2_2") (pintype "passive"))
    )
    (net (code "13") (name "Net-(IC1--INA)") (class "Default")
      (node (ref "IC1") (pin "1") (pinfunction "-INA_1") (pintype "input"))
      (node (ref "J1") (pin "2") (pinfunction "2_2") (pintype "passive"))
      (node (ref "P2") (pin "2") (pinfunction "2_2") (pintype "passive"))
      (node (ref "R8") (pin "1") (pinfunction "1_1") (pintype "passive"))
    )
    (net (code "14") (name "Net-(IC1--INB)") (class "Default")
      (node (ref "IC1") (pin "16") (pinfunction "-INB_16") (pintype "input"))
      (node (ref "J2") (pin "2") (pinfunction "2_2") (pintype "passive"))
      (node (ref "P2") (pin "4") (pinfunction "4_4") (pintype "passive"))
      (node (ref "R13") (pin "1") (pinfunction "1_1") (pintype "passive"))
    )
    (net (code "15") (name "Net-(IC1-OUTA)") (class "Default")
      (node (ref "IC1") (pin "6") (pinfunction "OUTA_6") (pintype "output"))
      (node (ref "IC1") (pin "7") (pinfunction "SENSEA_7") (pintype "passive"))
      (node (ref "OP1") (pin "3") (pinfunction "+IN1_3") (pintype "passive"))
    )
    (net (code "16") (name "Net-(IC1-OUTB)") (class "Default")
      (node (ref "IC1") (pin "10") (pinfunction "SENSEB_10") (pintype "passive"))
      (node (ref "IC1") (pin "11") (pinfunction "OUTB_11") (pintype "output"))
      (node (ref "OP1") (pin "5") (pinfunction "+IN2_5") (pintype "passive"))
    )
    (net (code "17") (name "Net-(IC1-RGA)") (class "Default")
      (node (ref "IC1") (pin "3") (pinfunction "RGA_3") (pintype "passive"))
      (node (ref "R3") (pin "2") (pinfunction "2_2") (pintype "passive"))
      (node (ref "R3") (pin "3") (pinfunction "3_3") (pintype "passive"))
    )
    (net (code "18") (name "Net-(IC1-RGA@1)") (class "Default")
      (node (ref "IC1") (pin "4") (pinfunction "RGA@1_4") (pintype "passive"))
      (node (ref "P1") (pin "1") (pinfunction "1_1") (pintype "passive"))
    )
    (net (code "19") (name "Net-(IC1-RGB)") (class "Default")
      (node (ref "IC1") (pin "14") (pinfunction "RGB_14") (pintype "passive"))
      (node (ref "R9") (pin "2") (pinfunction "2_2") (pintype "passive"))
      (node (ref "R9") (pin "3") (pinfunction "3_3") (pintype "passive"))
    )
    (net (code "20") (name "Net-(IC1-RGB@1)") (class "Default")
      (node (ref "IC1") (pin "13") (pinfunction "RGB@1_13") (pintype "passive"))
      (node (ref "P3") (pin "1") (pinfunction "1_1") (pintype "passive"))
    )
    (net (code "21") (name "Net-(IC2-+INA)") (class "Default")
      (node (ref "IC2") (pin "2") (pinfunction "+INA_2") (pintype "input"))
      (node (ref "J3") (pin "1") (pinfunction "1_1") (pintype "passive"))
      (node (ref "P2") (pin "5") (pinfunction "5_5") (pintype "passive"))
      (node (ref "R23") (pin "2") (pinfunction "2_2") (pintype "passive"))
    )
    (net (code "22") (name "Net-(IC2-+INB)") (class "Default")
      (node (ref "IC2") (pin "15") (pinfunction "+INB_15") (pintype "input"))
      (node (ref "J5") (pin "1") (pinfunction "1_1") (pintype "passive"))
      (node (ref "P2") (pin "7") (pinfunction "7_7") (pintype "passive"))
      (node (ref "R28") (pin "2") (pinfunction "2_2") (pintype "passive"))
    )
    (net (code "23") (name "Net-(IC2--INA)") (class "Default")
      (node (ref "IC2") (pin "1") (pinfunction "-INA_1") (pintype "input"))
      (node (ref "J3") (pin "2") (pinfunction "2_2") (pintype "passive"))
      (node (ref "P2") (pin "6") (pinfunction "6_6") (pintype "passive"))
      (node (ref "R26") (pin "1") (pinfunction "1_1") (pintype "passive"))
    )
    (net (code "24") (name "Net-(IC2--INB)") (class "Default")
      (node (ref "IC2") (pin "16") (pinfunction "-INB_16") (pintype "input"))
      (node (ref "J5") (pin "2") (pinfunction "2_2") (pintype "passive"))
      (node (ref "P2") (pin "8") (pinfunction "8_8") (pintype "passive"))
      (node (ref "R31") (pin "1") (pinfunction "1_1") (pintype "passive"))
    )
    (net (code "25") (name "Net-(IC2-OUTA)") (class "Default")
      (node (ref "IC2") (pin "6") (pinfunction "OUTA_6") (pintype "output"))
      (node (ref "IC2") (pin "7") (pinfunction "SENSEA_7") (pintype "passive"))
      (node (ref "OP1") (pin "12") (pinfunction "+IN3_12") (pintype "passive"))
    )
    (net (code "26") (name "Net-(IC2-OUTB)") (class "Default")
      (node (ref "IC2") (pin "10") (pinfunction "SENSEB_10") (pintype "passive"))
      (node (ref "IC2") (pin "11") (pinfunction "OUTB_11") (pintype "output"))
      (node (ref "OP1") (pin "10") (pinfunction "+IN4_10") (pintype "passive"))
    )
    (net (code "27") (name "Net-(IC2-RGA)") (class "Default")
      (node (ref "IC2") (pin "3") (pinfunction "RGA_3") (pintype "passive"))
      (node (ref "R22") (pin "3") (pinfunction "3_3") (pintype "passive"))
    )
    (net (code "28") (name "Net-(IC2-RGA@1)") (class "Default")
      (node (ref "IC2") (pin "4") (pinfunction "RGA@1_4") (pintype "passive"))
      (node (ref "P4") (pin "1") (pinfunction "1_1") (pintype "passive"))
    )
    (net (code "29") (name "Net-(IC2-RGB)") (class "Default")
      (node (ref "IC2") (pin "14") (pinfunction "RGB_14") (pintype "passive"))
      (node (ref "R27") (pin "3") (pinfunction "3_3") (pintype "passive"))
    )
    (net (code "30") (name "Net-(IC2-RGB@1)") (class "Default")
      (node (ref "IC2") (pin "13") (pinfunction "RGB@1_13") (pintype "passive"))
      (node (ref "P9") (pin "1") (pinfunction "1_1") (pintype "passive"))
    )
    (net (code "31") (name "Net-(OP1--IN1)") (class "Default")
      (node (ref "OP1") (pin "2") (pinfunction "-IN1_2") (pintype "passive"))
      (node (ref "R17") (pin "1") (pinfunction "1_1") (pintype "passive"))
      (node (ref "R4") (pin "1") (pinfunction "1_1") (pintype "passive"))
    )
    (net (code "32") (name "Net-(OP1--IN2)") (class "Default")
      (node (ref "OP1") (pin "6") (pinfunction "-IN2_6") (pintype "passive"))
      (node (ref "R11") (pin "1") (pinfunction "1_1") (pintype "passive"))
      (node (ref "R14") (pin "1") (pinfunction "1_1") (pintype "passive"))
    )
    (net (code "33") (name "Net-(OP1--IN3)") (class "Default")
      (node (ref "OP1") (pin "13") (pinfunction "-IN3_13") (pintype "passive"))
      (node (ref "R21") (pin "1") (pinfunction "1_1") (pintype "passive"))
      (node (ref "R24") (pin "1") (pinfunction "1_1") (pintype "passive"))
    )
    (net (code "34") (name "Net-(OP1--IN4)") (class "Default")
      (node (ref "OP1") (pin "9") (pinfunction "-IN4_9") (pintype "passive"))
      (node (ref "R19") (pin "1") (pinfunction "1_1") (pintype "passive"))
      (node (ref "R29") (pin "1") (pinfunction "1_1") (pintype "passive"))
    )
    (net (code "35") (name "Net-(OP1-OUT1)") (class "Default")
      (node (ref "C1") (pin "1") (pinfunction "1_1") (pintype "passive"))
      (node (ref "OP1") (pin "1") (pinfunction "OUT1_1") (pintype "passive"))
      (node (ref "R4") (pin "2") (pinfunction "2_2") (pintype "passive"))
      (node (ref "R4") (pin "3") (pinfunction "3_3") (pintype "passive"))
    )
    (net (code "36") (name "Net-(OP1-OUT2)") (class "Default")
      (node (ref "C5") (pin "1") (pinfunction "1_1") (pintype "passive"))
      (node (ref "OP1") (pin "7") (pinfunction "OUT2_7") (pintype "passive"))
      (node (ref "R11") (pin "2") (pinfunction "2_2") (pintype "passive"))
      (node (ref "R11") (pin "3") (pinfunction "3_3") (pintype "passive"))
    )
    (net (code "37") (name "Net-(OP1-OUT3)") (class "Default")
      (node (ref "C13") (pin "1") (pinfunction "1_1") (pintype "passive"))
      (node (ref "OP1") (pin "14") (pinfunction "OUT3_14") (pintype "passive"))
      (node (ref "R24") (pin "2") (pinfunction "2_2") (pintype "passive"))
      (node (ref "R24") (pin "3") (pinfunction "3_3") (pintype "passive"))
    )
    (net (code "38") (name "Net-(OP1-OUT4)") (class "Default")
      (node (ref "C14") (pin "1") (pinfunction "1_1") (pintype "passive"))
      (node (ref "OP1") (pin "8") (pinfunction "OUT4_8") (pintype "passive"))
      (node (ref "R29") (pin "2") (pinfunction "2_2") (pintype "passive"))
      (node (ref "R29") (pin "3") (pinfunction "3_3") (pintype "passive"))
    )
    (net (code "39") (name "Net-(P1-Pad2)") (class "Default")
      (node (ref "P1") (pin "2") (pinfunction "2_2") (pintype "passive"))
      (node (ref "R3") (pin "1") (pinfunction "1_1") (pintype "passive"))
    )
    (net (code "40") (name "Net-(P3-Pad2)") (class "Default")
      (node (ref "P3") (pin "2") (pinfunction "2_2") (pintype "passive"))
      (node (ref "R9") (pin "1") (pinfunction "1_1") (pintype "passive"))
    )
    (net (code "41") (name "Net-(P4-Pad2)") (class "Default")
      (node (ref "P4") (pin "2") (pinfunction "2_2") (pintype "passive"))
      (node (ref "R22") (pin "1") (pinfunction "1_1") (pintype "passive"))
      (node (ref "R22") (pin "2") (pinfunction "2_2") (pintype "passive"))
    )
    (net (code "42") (name "Net-(P9-Pad2)") (class "Default")
      (node (ref "P9") (pin "2") (pinfunction "2_2") (pintype "passive"))
      (node (ref "R27") (pin "1") (pinfunction "1_1") (pintype "passive"))
      (node (ref "R27") (pin "2") (pinfunction "2_2") (pintype "passive"))
    )
    (net (code "43") (name "Net-(U1-FB)") (class "Default")
      (node (ref "C4") (pin "2") (pinfunction "2_2") (pintype "passive"))
      (node (ref "R1") (pin "1") (pinfunction "1_1") (pintype "passive"))
      (node (ref "R7") (pin "2") (pinfunction "2_2") (pintype "passive"))
      (node (ref "U1") (pin "4") (pinfunction "FB_4") (pintype "input"))
    )
    (net (code "44") (name "Net-(U2-FB)") (class "Default")
      (node (ref "C9") (pin "1") (pinfunction "1_1") (pintype "passive"))
      (node (ref "R15") (pin "1") (pinfunction "1_1") (pintype "passive"))
      (node (ref "R18") (pin "2") (pinfunction "2_2") (pintype "passive"))
      (node (ref "U2") (pin "4") (pinfunction "FB_4") (pintype "input"))
    )
    (net (code "45") (name "Vbat+") (class "Default")
      (node (ref "C2") (pin "1") (pinfunction "1_1") (pintype "passive"))
      (node (ref "C8") (pin "1") (pinfunction "1_1") (pintype "passive"))
      (node (ref "J4") (pin "1") (pinfunction "1_1") (pintype "passive"))
      (node (ref "U1") (pin "7") (pinfunction "VIN_7") (pintype "input"))
      (node (ref "U2") (pin "7") (pinfunction "VIN_7") (pintype "input"))
    )
    (net (code "46") (name "unconnected-(P5-Pad1)") (class "Default")
      (node (ref "P5") (pin "1") (pinfunction "1_1") (pintype "passive"))
    )
    (net (code "47") (name "unconnected-(P5-Pad2)") (class "Default")
      (node (ref "P5") (pin "2") (pinfunction "2_2") (pintype "passive"))
    )
    (net (code "48") (name "unconnected-(P5-Pad3)") (class "Default")
      (node (ref "P5") (pin "3") (pinfunction "3_3") (pintype "passive"))
    )
    (net (code "49") (name "unconnected-(P5-Pad4)") (class "Default")
      (node (ref "P5") (pin "4") (pinfunction "4_4") (pintype "passive"))
    )
    (net (code "50") (name "unconnected-(P5-Pad5)") (class "Default")
      (node (ref "P5") (pin "5") (pinfunction "5_5") (pintype "passive"))
    )
    (net (code "51") (name "unconnected-(P5-Pad6)") (class "Default")
      (node (ref "P5") (pin "6") (pinfunction "6_6") (pintype "passive"))
    )
    (net (code "52") (name "unconnected-(P5-Pad7)") (class "Default")
      (node (ref "P5") (pin "7") (pinfunction "7_7") (pintype "passive"))
    )
    (net (code "53") (name "unconnected-(P5-Pad8)") (class "Default")
      (node (ref "P5") (pin "8") (pinfunction "8_8") (pintype "passive"))
    )
    (net (code "54") (name "unconnected-(P5-Pad9)") (class "Default")
      (node (ref "P5") (pin "9") (pinfunction "9_9") (pintype "passive"))
    )
    (net (code "55") (name "unconnected-(P5-Pad10)") (class "Default")
      (node (ref "P5") (pin "10") (pinfunction "10_10") (pintype "passive"))
    )
    (net (code "56") (name "unconnected-(P5-Pad11)") (class "Default")
      (node (ref "P5") (pin "11") (pinfunction "11_11") (pintype "passive"))
    )
    (net (code "57") (name "unconnected-(P5-Pad12)") (class "Default")
      (node (ref "P5") (pin "12") (pinfunction "12_12") (pintype "passive"))
    )
    (net (code "58") (name "unconnected-(P5-Pad13)") (class "Default")
      (node (ref "P5") (pin "13") (pinfunction "13_13") (pintype "passive"))
    )
    (net (code "59") (name "unconnected-(P5-Pad14)") (class "Default")
      (node (ref "P5") (pin "14") (pinfunction "14_14") (pintype "passive"))
    )
    (net (code "60") (name "unconnected-(P5-Pad15)") (class "Default")
      (node (ref "P5") (pin "15") (pinfunction "15_15") (pintype "passive"))
    )
    (net (code "61") (name "unconnected-(P5-Pad16)") (class "Default")
      (node (ref "P5") (pin "16") (pinfunction "16_16") (pintype "passive"))
    )
    (net (code "62") (name "unconnected-(P5-Pad17)") (class "Default")
      (node (ref "P5") (pin "17") (pinfunction "17_17") (pintype "passive"))
    )
    (net (code "63") (name "unconnected-(P5-Pad18)") (class "Default")
      (node (ref "P5") (pin "18") (pinfunction "18_18") (pintype "passive"))
    )
    (net (code "64") (name "unconnected-(P5-Pad19)") (class "Default")
      (node (ref "P5") (pin "19") (pinfunction "19_19") (pintype "passive"))
    )
    (net (code "65") (name "unconnected-(P5-Pad20)") (class "Default")
      (node (ref "P5") (pin "20") (pinfunction "20_20") (pintype "passive"))
    )
    (net (code "66") (name "unconnected-(P6-Pad1)") (class "Default")
      (node (ref "P6") (pin "1") (pinfunction "1_1") (pintype "passive"))
    )
    (net (code "67") (name "unconnected-(P6-Pad2)") (class "Default")
      (node (ref "P6") (pin "2") (pinfunction "2_2") (pintype "passive"))
    )
    (net (code "68") (name "unconnected-(P6-Pad3)") (class "Default")
      (node (ref "P6") (pin "3") (pinfunction "3_3") (pintype "passive"))
    )
    (net (code "69") (name "unconnected-(P6-Pad4)") (class "Default")
      (node (ref "P6") (pin "4") (pinfunction "4_4") (pintype "passive"))
    )
    (net (code "70") (name "unconnected-(P6-Pad5)") (class "Default")
      (node (ref "P6") (pin "5") (pinfunction "5_5") (pintype "passive"))
    )
    (net (code "71") (name "unconnected-(P6-Pad6)") (class "Default")
      (node (ref "P6") (pin "6") (pinfunction "6_6") (pintype "passive"))
    )
    (net (code "72") (name "unconnected-(P6-Pad8)") (class "Default")
      (node (ref "P6") (pin "8") (pinfunction "8_8") (pintype "passive"))
    )
    (net (code "73") (name "unconnected-(P6-Pad9)") (class "Default")
      (node (ref "P6") (pin "9") (pinfunction "9_9") (pintype "passive"))
    )
    (net (code "74") (name "unconnected-(P6-Pad10)") (class "Default")
      (node (ref "P6") (pin "10") (pinfunction "10_10") (pintype "passive"))
    )
    (net (code "75") (name "unconnected-(P6-Pad12)") (class "Default")
      (node (ref "P6") (pin "12") (pinfunction "12_12") (pintype "passive"))
    )
    (net (code "76") (name "unconnected-(P6-Pad14)") (class "Default")
      (node (ref "P6") (pin "14") (pinfunction "14_14") (pintype "passive"))
    )
    (net (code "77") (name "unconnected-(P6-Pad16)") (class "Default")
      (node (ref "P6") (pin "16") (pinfunction "16_16") (pintype "passive"))
    )
    (net (code "78") (name "unconnected-(P7-Pad2)") (class "Default")
      (node (ref "P7") (pin "2") (pinfunction "2_2") (pintype "passive"))
    )
    (net (code "79") (name "unconnected-(P7-Pad4)") (class "Default")
      (node (ref "P7") (pin "4") (pinfunction "4_4") (pintype "passive"))
    )
    (net (code "80") (name "unconnected-(P7-Pad6)") (class "Default")
      (node (ref "P7") (pin "6") (pinfunction "6_6") (pintype "passive"))
    )
    (net (code "81") (name "unconnected-(P7-Pad8)") (class "Default")
      (node (ref "P7") (pin "8") (pinfunction "8_8") (pintype "passive"))
    )
    (net (code "82") (name "unconnected-(P7-Pad9)") (class "Default")
      (node (ref "P7") (pin "9") (pinfunction "9_9") (pintype "passive"))
    )
    (net (code "83") (name "unconnected-(P7-Pad10)") (class "Default")
      (node (ref "P7") (pin "10") (pinfunction "10_10") (pintype "passive"))
    )
    (net (code "84") (name "unconnected-(P7-Pad11)") (class "Default")
      (node (ref "P7") (pin "11") (pinfunction "11_11") (pintype "passive"))
    )
    (net (code "85") (name "unconnected-(P7-Pad12)") (class "Default")
      (node (ref "P7") (pin "12") (pinfunction "12_12") (pintype "passive"))
    )
    (net (code "86") (name "unconnected-(P7-Pad13)") (class "Default")
      (node (ref "P7") (pin "13") (pinfunction "13_13") (pintype "passive"))
    )
    (net (code "87") (name "unconnected-(P7-Pad14)") (class "Default")
      (node (ref "P7") (pin "14") (pinfunction "14_14") (pintype "passive"))
    )
    (net (code "88") (name "unconnected-(P7-Pad15)") (class "Default")
      (node (ref "P7") (pin "15") (pinfunction "15_15") (pintype "passive"))
    )
    (net (code "89") (name "unconnected-(P7-Pad16)") (class "Default")
      (node (ref "P7") (pin "16") (pinfunction "16_16") (pintype "passive"))
    )
    (net (code "90") (name "unconnected-(P7-Pad17)") (class "Default")
      (node (ref "P7") (pin "17") (pinfunction "17_17") (pintype "passive"))
    )
    (net (code "91") (name "unconnected-(P7-Pad18)") (class "Default")
      (node (ref "P7") (pin "18") (pinfunction "18_18") (pintype "passive"))
    )
    (net (code "92") (name "unconnected-(P7-Pad19)") (class "Default")
      (node (ref "P7") (pin "19") (pinfunction "19_19") (pintype "passive"))
    )
    (net (code "93") (name "unconnected-(P7-Pad20)") (class "Default")
      (node (ref "P7") (pin "20") (pinfunction "20_20") (pintype "passive"))
    )
    (net (code "94") (name "unconnected-(P7-Pad21)") (class "Default")
      (node (ref "P7") (pin "21") (pinfunction "21_21") (pintype "passive"))
    )
    (net (code "95") (name "unconnected-(P7-Pad22)") (class "Default")
      (node (ref "P7") (pin "22") (pinfunction "22_22") (pintype "passive"))
    )
    (net (code "96") (name "unconnected-(P7-Pad23)") (class "Default")
      (node (ref "P7") (pin "23") (pinfunction "23_23") (pintype "passive"))
    )
    (net (code "97") (name "unconnected-(P7-Pad24)") (class "Default")
      (node (ref "P7") (pin "24") (pinfunction "24_24") (pintype "passive"))
    )
    (net (code "98") (name "unconnected-(P7-Pad25)") (class "Default")
      (node (ref "P7") (pin "25") (pinfunction "25_25") (pintype "passive"))
    )
    (net (code "99") (name "unconnected-(P7-Pad26)") (class "Default")
      (node (ref "P7") (pin "26") (pinfunction "26_26") (pintype "passive"))
    )
    (net (code "100") (name "unconnected-(P7-Pad27)") (class "Default")
      (node (ref "P7") (pin "27") (pinfunction "27_27") (pintype "passive"))
    )
    (net (code "101") (name "unconnected-(P7-Pad28)") (class "Default")
      (node (ref "P7") (pin "28") (pinfunction "28_28") (pintype "passive"))
    )
    (net (code "102") (name "unconnected-(P7-Pad29)") (class "Default")
      (node (ref "P7") (pin "29") (pinfunction "29_29") (pintype "passive"))
    )
    (net (code "103") (name "unconnected-(P7-Pad30)") (class "Default")
      (node (ref "P7") (pin "30") (pinfunction "30_30") (pintype "passive"))
    )
    (net (code "104") (name "unconnected-(P8-Pad1)") (class "Default")
      (node (ref "P8") (pin "1") (pinfunction "1_1") (pintype "passive"))
    )
    (net (code "105") (name "unconnected-(P8-Pad2)") (class "Default")
      (node (ref "P8") (pin "2") (pinfunction "2_2") (pintype "passive"))
    )
    (net (code "106") (name "unconnected-(P8-Pad3)") (class "Default")
      (node (ref "P8") (pin "3") (pinfunction "3_3") (pintype "passive"))
    )
    (net (code "107") (name "unconnected-(P8-Pad4)") (class "Default")
      (node (ref "P8") (pin "4") (pinfunction "4_4") (pintype "passive"))
    )
    (net (code "108") (name "unconnected-(P8-Pad5)") (class "Default")
      (node (ref "P8") (pin "5") (pinfunction "5_5") (pintype "passive"))
    )
    (net (code "109") (name "unconnected-(P8-Pad6)") (class "Default")
      (node (ref "P8") (pin "6") (pinfunction "6_6") (pintype "passive"))
    )
    (net (code "110") (name "unconnected-(P8-Pad7)") (class "Default")
      (node (ref "P8") (pin "7") (pinfunction "7_7") (pintype "passive"))
    )
    (net (code "111") (name "unconnected-(P8-Pad8)") (class "Default")
      (node (ref "P8") (pin "8") (pinfunction "8_8") (pintype "passive"))
    )
    (net (code "112") (name "unconnected-(P8-Pad9)") (class "Default")
      (node (ref "P8") (pin "9") (pinfunction "9_9") (pintype "passive"))
    )
    (net (code "113") (name "unconnected-(P8-Pad10)") (class "Default")
      (node (ref "P8") (pin "10") (pinfunction "10_10") (pintype "passive"))
    )
    (net (code "114") (name "unconnected-(P8-Pad11)") (class "Default")
      (node (ref "P8") (pin "11") (pinfunction "11_11") (pintype "passive"))
    )
    (net (code "115") (name "unconnected-(P8-Pad12)") (class "Default")
      (node (ref "P8") (pin "12") (pinfunction "12_12") (pintype "passive"))
    )
    (net (code "116") (name "unconnected-(P8-Pad13)") (class "Default")
      (node (ref "P8") (pin "13") (pinfunction "13_13") (pintype "passive"))
    )
    (net (code "117") (name "unconnected-(P8-Pad14)") (class "Default")
      (node (ref "P8") (pin "14") (pinfunction "14_14") (pintype "passive"))
    )
    (net (code "118") (name "unconnected-(P8-Pad15)") (class "Default")
      (node (ref "P8") (pin "15") (pinfunction "15_15") (pintype "passive"))
    )
    (net (code "119") (name "unconnected-(P8-Pad16)") (class "Default")
      (node (ref "P8") (pin "16") (pinfunction "16_16") (pintype "passive"))
    )
    (net (code "120") (name "unconnected-(P8-Pad17)") (class "Default")
      (node (ref "P8") (pin "17") (pinfunction "17_17") (pintype "passive"))
    )
    (net (code "121") (name "unconnected-(P8-Pad18)") (class "Default")
      (node (ref "P8") (pin "18") (pinfunction "18_18") (pintype "passive"))
    )
    (net (code "122") (name "unconnected-(P8-Pad19)") (class "Default")
      (node (ref "P8") (pin "19") (pinfunction "19_19") (pintype "passive"))
    )
    (net (code "123") (name "unconnected-(P8-Pad20)") (class "Default")
      (node (ref "P8") (pin "20") (pinfunction "20_20") (pintype "passive"))
    )
    (net (code "124") (name "unconnected-(P8-Pad21)") (class "Default")
      (node (ref "P8") (pin "21") (pinfunction "21_21") (pintype "passive"))
    )
    (net (code "125") (name "unconnected-(P8-Pad22)") (class "Default")
      (node (ref "P8") (pin "22") (pinfunction "22_22") (pintype "passive"))
    )
    (net (code "126") (name "unconnected-(P8-Pad23)") (class "Default")
      (node (ref "P8") (pin "23") (pinfunction "23_23") (pintype "passive"))
    )
    (net (code "127") (name "unconnected-(P8-Pad24)") (class "Default")
      (node (ref "P8") (pin "24") (pinfunction "24_24") (pintype "passive"))
    )
    (net (code "128") (name "unconnected-(P8-Pad25)") (class "Default")
      (node (ref "P8") (pin "25") (pinfunction "25_25") (pintype "passive"))
    )
    (net (code "129") (name "unconnected-(P8-Pad26)") (class "Default")
      (node (ref "P8") (pin "26") (pinfunction "26_26") (pintype "passive"))
    )
    (net (code "130") (name "unconnected-(P8-Pad27)") (class "Default")
      (node (ref "P8") (pin "27") (pinfunction "27_27") (pintype "passive"))
    )
    (net (code "131") (name "unconnected-(P8-Pad28)") (class "Default")
      (node (ref "P8") (pin "28") (pinfunction "28_28") (pintype "passive"))
    )
    (net (code "132") (name "unconnected-(P8-Pad29)") (class "Default")
      (node (ref "P8") (pin "29") (pinfunction "29_29") (pintype "passive"))
    )
    (net (code "133") (name "unconnected-(P8-Pad30)") (class "Default")
      (node (ref "P8") (pin "30") (pinfunction "30_30") (pintype "passive"))
    )
    (net (code "134") (name "unconnected-(P8-Pad31)") (class "Default")
      (node (ref "P8") (pin "31") (pinfunction "31_31") (pintype "passive"))
    )
    (net (code "135") (name "unconnected-(P8-Pad32)") (class "Default")
      (node (ref "P8") (pin "32") (pinfunction "32_32") (pintype "passive"))
    )
    (net (code "136") (name "unconnected-(P8-Pad33)") (class "Default")
      (node (ref "P8") (pin "33") (pinfunction "33_33") (pintype "passive"))
    )
    (net (code "137") (name "unconnected-(P8-Pad34)") (class "Default")
      (node (ref "P8") (pin "34") (pinfunction "34_34") (pintype "passive"))
    )
  )
)
